# Schematic_R1.net
KiCad netlist of a schematic drawn in Altium Designer
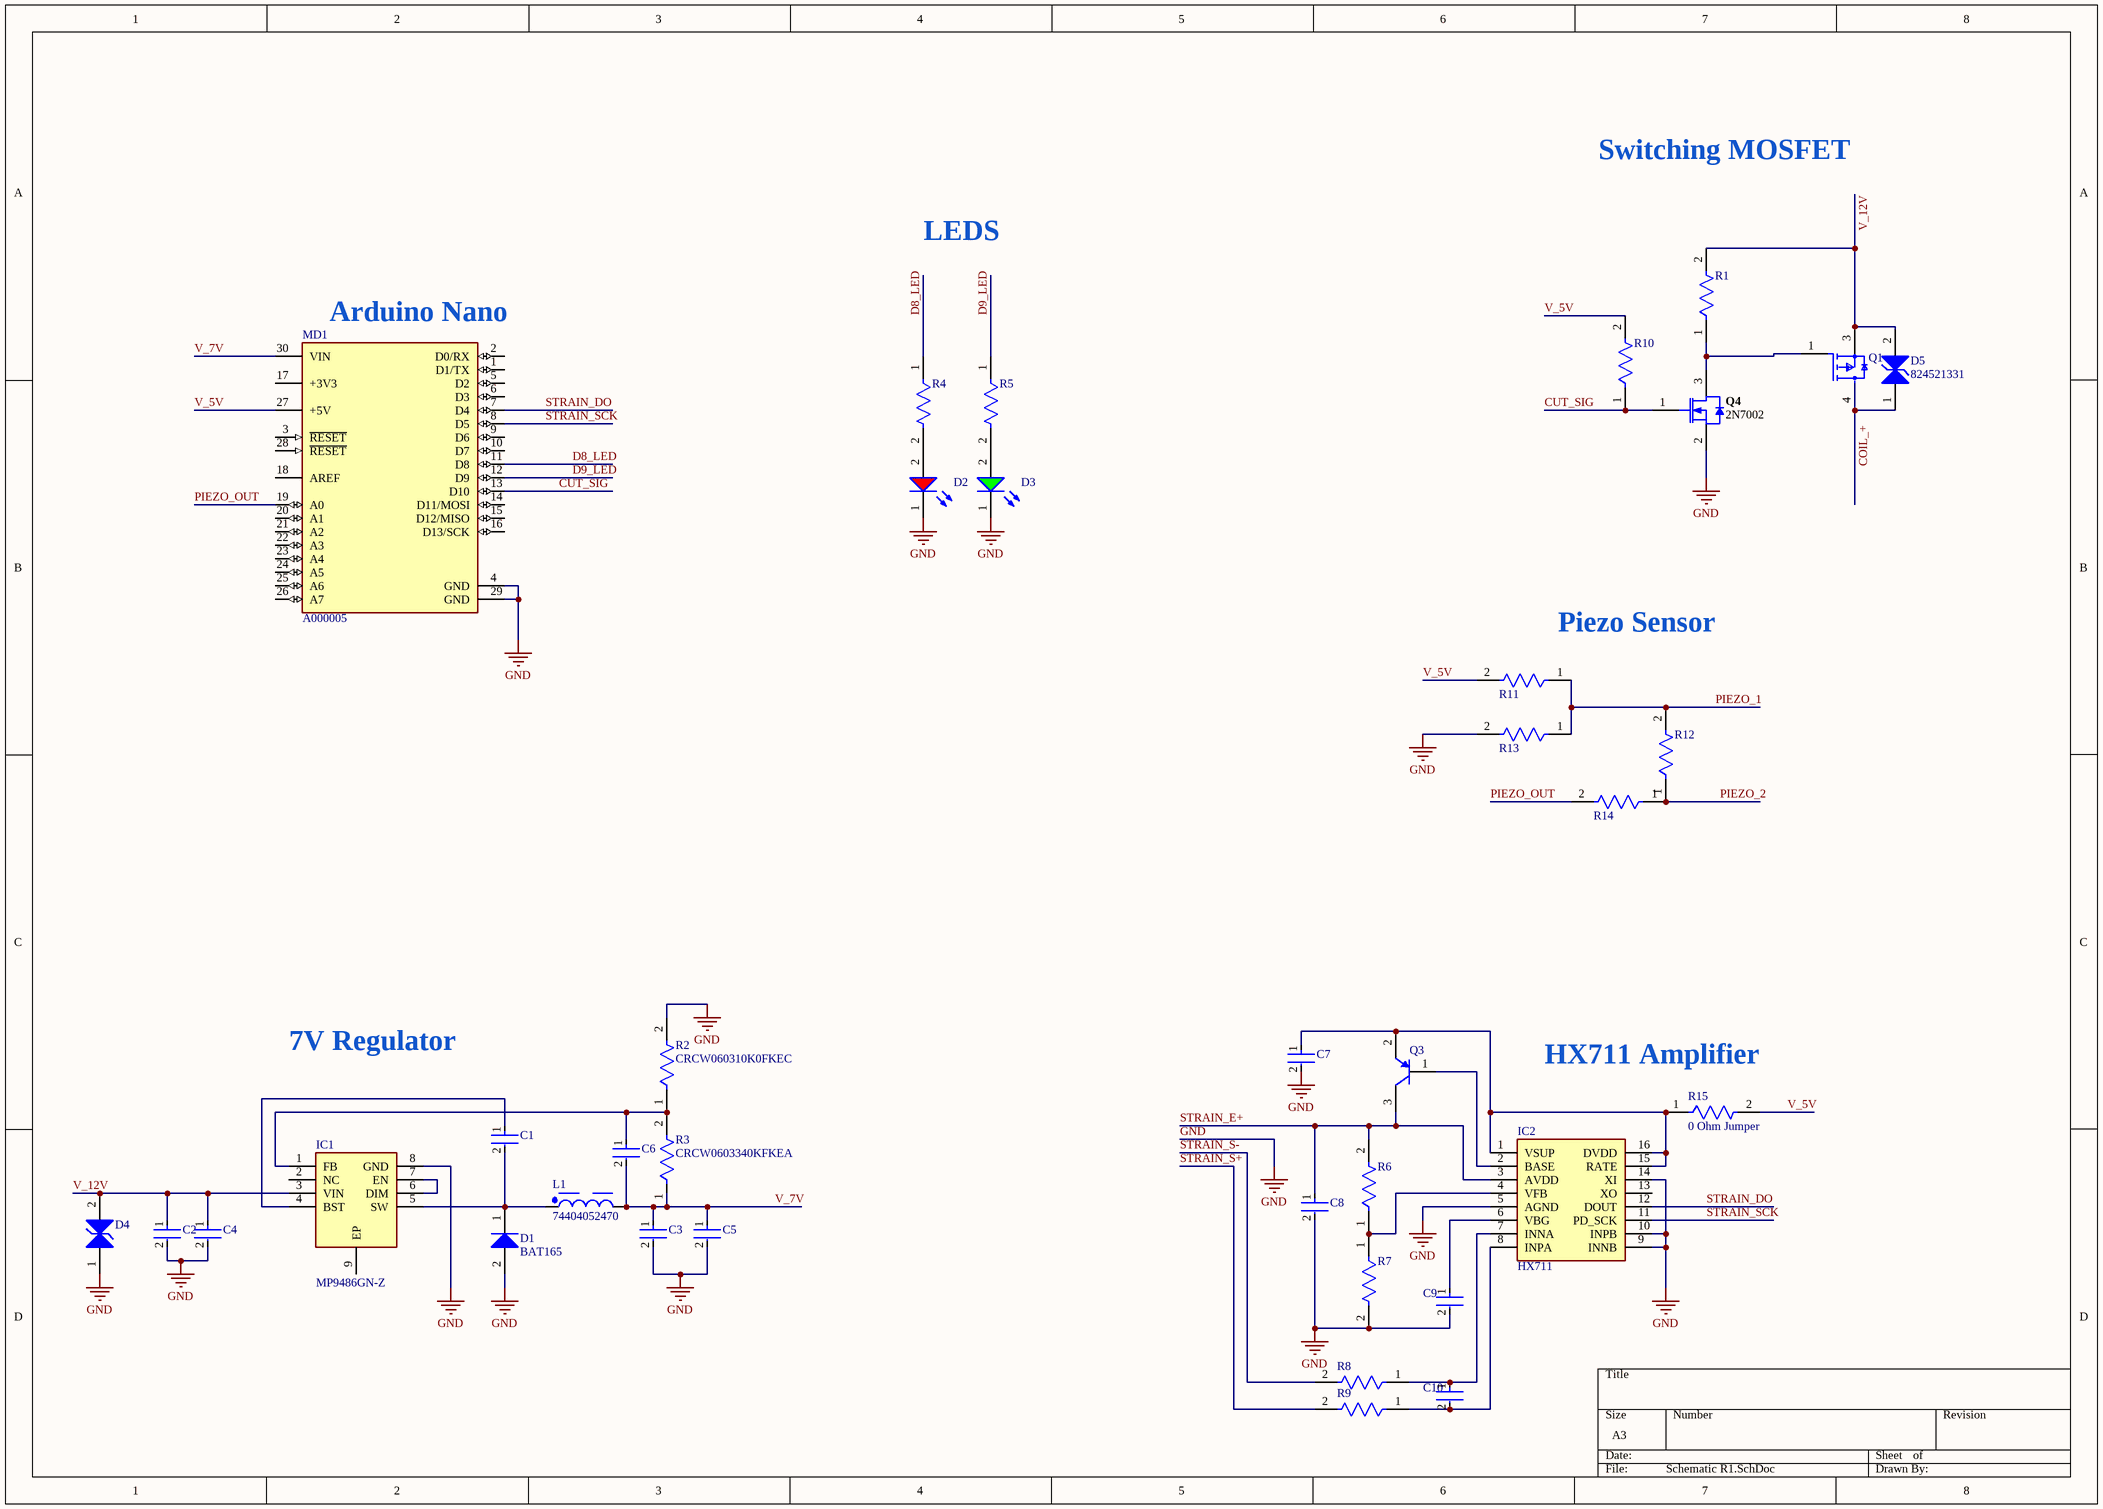
[diagram p0: Schematic R1.SchDoc]

(export (version "E")
  (design (tool "Eeschema 10.0.6"))
  (components
    (comp (ref "C1")
      (value "C0603C104K3PACTU")
      (footprint "FP-C0603C-CF-MFG")
      (description "C0603 0.10 μF X5R 30ppm/°C 10.00% 25 V")
      (fields
        (field (name "TOLERANCE") "0.1")
        (field (name "OCTOPART") "https://octopart.com/c0603c104k3pactu-kemet-19022554")
      )
      (libsource (lib "Altium Content Vault") (part "b4654b650e69147ec39a6b967a45e02"))
    )
    (comp (ref "C2")
      (value "C3216X5R1E476M160AC")
      (footprint "FP-C3216-160-0_2-MFG")
      (description "Multilayer Ceramic Capacitors 47uF ±20% 25V X5R SMD 1206")
      (fields (field (name "VOLTAGE") "25V") (field (name "TOLERANCE") "20%"))
      (libsource (lib "Altium Content Vault") (part "11868f565c42a9108669ba33697ecf6"))
    )
    (comp (ref "C3")
      (value "C3216X5R1E476M160AC")
      (footprint "FP-C3216-160-0_2-MFG")
      (description "Multilayer Ceramic Capacitors 47uF ±20% 25V X5R SMD 1206")
      (fields (field (name "VOLTAGE") "25V") (field (name "TOLERANCE") "20%"))
      (libsource (lib "Altium Content Vault") (part "11868f565c42a9108669ba33697ecf6"))
    )
    (comp (ref "C4")
      (value "C0603C104K3PACTU")
      (footprint "FP-C0603C-CF-MFG")
      (description "C0603 0.10 μF X5R 30ppm/°C 10.00% 25 V")
      (fields
        (field (name "TOLERANCE") "0.1")
        (field (name "OCTOPART") "https://octopart.com/c0603c104k3pactu-kemet-19022554")
      )
      (libsource (lib "Altium Content Vault") (part "b4654b650e69147ec39a6b967a45e02"))
    )
    (comp (ref "C5")
      (value "C0603C225K4PACTU")
      (footprint "FP-C0603C225K4PACTU-MFG")
      (description "CAP CER 2.2UF 16V X5R 0603")
      (fields (field (name "TOLERANCE") "10%") (field (name "VOLTAGE") "16V"))
      (libsource (lib "Altium Content Vault") (part "b4654b650e69147ec39a6b967a45e02"))
    )
    (comp (ref "C6")
      (value "C0603C104K3PACTU")
      (footprint "FP-C0603C-CF-MFG")
      (description "C0603 0.10 μF X5R 30ppm/°C 10.00% 25 V")
      (fields
        (field (name "TOLERANCE") "0.1")
        (field (name "OCTOPART") "https://octopart.com/c0603c104k3pactu-kemet-19022554")
      )
      (libsource (lib "Altium Content Vault") (part "b4654b650e69147ec39a6b967a45e02"))
    )
    (comp (ref "C7")
      (value "C0603C106M8PACTU")
      (footprint "FP-C0603C106M8PACTU-MFG")
      (description "CAP CER 10UF 10V X5R 0603")
      (libsource (lib "Altium Content Vault") (part "02cd4be3c70576c341d710602a673aa"))
    )
    (comp (ref "C8")
      (value "C0603C106M8PACTU")
      (footprint "FP-C0603C106M8PACTU-MFG")
      (description "CAP CER 10UF 10V X5R 0603")
      (libsource (lib "Altium Content Vault") (part "02cd4be3c70576c341d710602a673aa"))
    )
    (comp (ref "C9")
      (value "C0603C104K3PACTU")
      (footprint "FP-C0603C-CF-MFG")
      (description "C0603 0.10 μF X5R 30ppm/°C 10.00% 25 V")
      (fields
        (field (name "TOLERANCE") "0.1")
        (field (name "OCTOPART") "https://octopart.com/c0603c104k3pactu-kemet-19022554")
      )
      (libsource (lib "Altium Content Vault") (part "b4654b650e69147ec39a6b967a45e02"))
    )
    (comp (ref "C10")
      (value "C0603C104K3PACTU")
      (footprint "FP-C0603C-CF-MFG")
      (description "C0603 0.10 μF X5R 30ppm/°C 10.00% 25 V")
      (fields
        (field (name "TOLERANCE") "0.1")
        (field (name "OCTOPART") "https://octopart.com/c0603c104k3pactu-kemet-19022554")
      )
      (libsource (lib "Altium Content Vault") (part "b4654b650e69147ec39a6b967a45e02"))
    )
    (comp (ref "D1")
      (value "BAT165")
      (footprint "INF-SOD323_V")
      (description "Medium Power AF Schottky Diode, SOD323, Reel, Green")
      (fields (field (name "MANUFACTURER") "Infineon"))
      (libsource (lib "Altium Content Vault") (part "INF-D_K1A2-2"))
    )
    (comp (ref "D2")
      (value "150080RS75000")
      (footprint "WL-SMCW_0805_150080xx75000")
      (libsource (lib "Altium Content Vault") (part "LED_Red_2A-1K"))
    )
    (comp (ref "D3")
      (value "150080GS75000")
      (footprint "WL-SMCW_0805_150080xx75000")
      (libsource (lib "Altium Content Vault") (part "LED_Green_2A-1K"))
    )
    (comp (ref "D4")
      (value "824521331")
      (footprint "WE-TVSP_DO-214AA_Bidirectional")
      (description "824521331 TVS diode [Würth Elektronik] 824521331 TVS diode")
      (libsource (lib "Altium Content Vault") (part "WE-TVSP_Bidirectional"))
    )
    (comp (ref "D5")
      (value "824521331")
      (footprint "WE-TVSP_DO-214AA_Bidirectional")
      (description "824521331 TVS diode [Würth Elektronik] 824521331 TVS diode")
      (libsource (lib "Altium Content Vault") (part "WE-TVSP_Bidirectional"))
    )
    (comp (ref "IC1")
      (value "MP9486GN-Z")
      (footprint "SamacSys:SOIC127P600X170-9N")
      (description "Integrated Circuit")
      (fields (field (name "MOUSER PART NUMBER") "946-MP9486GN-Z"))
      (libsource (lib "*") (part "MP9486GN-Z"))
    )
    (comp (ref "IC2")
      (value "HX711")
      (footprint "SamacSys:SOIC127P600X160-16N")
      (description "Integrated Circuit")
      (libsource (lib "*") (part "HX711"))
    )
    (comp (ref "L1")
      (value "74404052470")
      (footprint "WE-LQS_5020")
      (description "74404052470 Inductors, Fixed, WE-LQS SMD 5020 47uH 0.8A 521mOhms")
      (fields (field (name "TOLERANCE") "20%"))
      (libsource (lib "Altium Content Vault") (part "Inductor - 2"))
    )
    (comp (ref "MD1")
      (value "A000005")
      (footprint "FP-A000005-MFG")
      (description "ARDUINO NANO ATMEGA328 EVAL BRD")
      (libsource (lib "Altium Content Vault") (part "d190c066e99afd1c6882cf92e11b2cc"))
    )
    (comp (ref "Q1")
      (value "SQM120P06-07L_GE3")
      (footprint "FP-T13-0707-MFG")
      (description "MOSFET P-CH 60V 120A TO263")
      (fields
        (field (name "MANUFACTURER") "Vishay")
        (field (name "OCTOPART") "https://octopart.com/sqm120p06-07l_ge3-vishay-61925110")
      )
      (libsource (lib "Altium Content Vault") (part "b4396205e6ce7dccbaef9df51870b92"))
    )
    (comp (ref "Q3")
      (value "MMBT4403LT1G")
      (footprint "ONSC-SOT-23-3-318-08_V")
      (description "Switching Transistor, PNP Silicon, 3-Pin SOT-23, Pb-Free, Tape and Reel")
      (fields (field (name "MANUFACTURER") "On Semiconductor"))
      (libsource (lib "Altium Content Vault") (part "ONSC-PNP-B1E2C3-3"))
    )
    (comp (ref "Q4")
      (value "2N7002")
      (footprint "INF-PG-SOT23_M")
      (fields (field (name "MANUFACTURER") "Infineon"))
      (libsource (lib "Altium Content Vault") (part "INF-NDMOS-GSD-3"))
    )
    (comp (ref "R1")
      (value "CRCW060310K0FKEC")
      (footprint "FP-CRCW0603-e3-IPC_A")
      (description "RES Thick Film, 10kΩ, 1%, 0.1W, 100ppm/°C, 0603")
      (fields (field (name "TOLERANCE") "1%"))
      (libsource (lib "Altium Content Vault") (part "1029c3af85768c4190bb7ad29bc67b5"))
    )
    (comp (ref "R2")
      (value "CRCW060310K0FKEC")
      (footprint "FP-CRCW0603-e3-IPC_A")
      (description "RES Thick Film, 10kΩ, 1%, 0.1W, 100ppm/°C, 0603")
      (fields (field (name "TOLERANCE") "1%"))
      (libsource (lib "Altium Content Vault") (part "1029c3af85768c4190bb7ad29bc67b5"))
    )
    (comp (ref "R3")
      (value "CRCW0603340KFKEA")
      (footprint "FP-CRCW0603-e3-IPC_C")
      (description "RES Thick Film, 340kΩ, 1%, 0.1W, 100ppm/°C, 0603")
      (fields (field (name "TOLERANCE") "1%"))
      (libsource (lib "Altium Content Vault") (part "1029c3af85768c4190bb7ad29bc67b5"))
    )
    (comp (ref "R4")
      (value "CRCW0603470RFKEA")
      (footprint "FP-CRCW0603-e3-MFG")
      (description "RES Thick Film, 470Ω, 1%, 0.1W, 100ppm/°C, 0603")
      (fields (field (name "TOLERANCE") "1%"))
      (libsource (lib "Altium Content Vault") (part "1029c3af85768c4190bb7ad29bc67b5"))
    )
    (comp (ref "R5")
      (value "CRCW0603470RFKEA")
      (footprint "FP-CRCW0603-e3-MFG")
      (description "RES Thick Film, 470Ω, 1%, 0.1W, 100ppm/°C, 0603")
      (fields (field (name "TOLERANCE") "1%"))
      (libsource (lib "Altium Content Vault") (part "1029c3af85768c4190bb7ad29bc67b5"))
    )
    (comp (ref "R6")
      (value "CRCW060310K0FKEC")
      (footprint "FP-CRCW0603-e3-IPC_A")
      (description "RES Thick Film, 10kΩ, 1%, 0.1W, 100ppm/°C, 0603")
      (fields (field (name "TOLERANCE") "1%"))
      (libsource (lib "Altium Content Vault") (part "1029c3af85768c4190bb7ad29bc67b5"))
    )
    (comp (ref "R7")
      (value "CRCW06038K20FKEC")
      (footprint "FP-CRCW0603-e3-IPC_B")
      (description "RES Thick Film, 8.2kΩ, 1%, 0.1W, 100ppm/°C, 0603")
      (fields (field (name "TOLERANCE") "1%"))
      (libsource (lib "Altium Content Vault") (part "1029c3af85768c4190bb7ad29bc67b5"))
    )
    (comp (ref "R8")
      (value "CRCW0603100RFKEB")
      (footprint "FP-CRCW0603-e3-IPC_A")
      (description "RES Thick Film, 100Ω, 1%, 0.1W, 100ppm/°C, 0603")
      (fields (field (name "TOLERANCE") "1%"))
      (libsource (lib "Altium Content Vault") (part "1029c3af85768c4190bb7ad29bc67b5"))
    )
    (comp (ref "R9")
      (value "CRCW0603100RFKEB")
      (footprint "FP-CRCW0603-e3-IPC_A")
      (description "RES Thick Film, 100Ω, 1%, 0.1W, 100ppm/°C, 0603")
      (fields (field (name "TOLERANCE") "1%"))
      (libsource (lib "Altium Content Vault") (part "1029c3af85768c4190bb7ad29bc67b5"))
    )
    (comp (ref "R10")
      (value "CRCW060310K0FKEC")
      (footprint "FP-CRCW0603-e3-IPC_A")
      (description "RES Thick Film, 10kΩ, 1%, 0.1W, 100ppm/°C, 0603")
      (fields (field (name "TOLERANCE") "1%"))
      (libsource (lib "Altium Content Vault") (part "1029c3af85768c4190bb7ad29bc67b5"))
    )
    (comp (ref "R11")
      (value "CRCW060310K0FKEC")
      (footprint "FP-CRCW0603-e3-IPC_A")
      (description "RES Thick Film, 10kΩ, 1%, 0.1W, 100ppm/°C, 0603")
      (fields (field (name "TOLERANCE") "1%"))
      (libsource (lib "Altium Content Vault") (part "1029c3af85768c4190bb7ad29bc67b5"))
    )
    (comp (ref "R12")
      (value "CRCW060310M0JNEA")
      (footprint "FP-CRCW0603-e3-IPC_A")
      (description "RES Thick Film, 10MΩ, 5%, 0.1W, 200ppm/°C, 0603")
      (fields (field (name "TOLERANCE") "5%"))
      (libsource (lib "Altium Content Vault") (part "1029c3af85768c4190bb7ad29bc67b5"))
    )
    (comp (ref "R13")
      (value "CRCW060310K0FKEC")
      (footprint "FP-CRCW0603-e3-IPC_A")
      (description "RES Thick Film, 10kΩ, 1%, 0.1W, 100ppm/°C, 0603")
      (fields (field (name "TOLERANCE") "1%"))
      (libsource (lib "Altium Content Vault") (part "1029c3af85768c4190bb7ad29bc67b5"))
    )
    (comp (ref "R14")
      (value "CRCW060310K0FKEC")
      (footprint "FP-CRCW0603-e3-IPC_A")
      (description "RES Thick Film, 10kΩ, 1%, 0.1W, 100ppm/°C, 0603")
      (fields (field (name "TOLERANCE") "1%"))
      (libsource (lib "Altium Content Vault") (part "1029c3af85768c4190bb7ad29bc67b5"))
    )
    (comp (ref "R15")
      (value "0 Ohm Jumper")
      (footprint "FP-CRCW0603-HPe3-IPC_B")
      (description "RES Thick Film, 0Ω, 5%, 0.33W, 200ppm/°C, 0603")
      (libsource (lib "Altium Content Vault") (part "1029c3af85768c4190bb7ad29bc67b5"))
    )
  )
  (nets
    (net (code "1") (name "/COIL_+") (class "Default")
      (node (ref "D5") (pin "1") (pinfunction "1_1") (pintype "passive"))
      (node (ref "Q1") (pin "4") (pinfunction "D_4") (pintype "passive"))
    )
    (net (code "2") (name "/CUT_SIG") (class "Default")
      (node (ref "MD1") (pin "13") (pinfunction "D10_13") (pintype "bidirectional"))
      (node (ref "Q4") (pin "1") (pinfunction "GATE_1") (pintype "passive"))
      (node (ref "R10") (pin "1") (pinfunction "1_1") (pintype "passive"))
    )
    (net (code "3") (name "/D8_LED") (class "Default")
      (node (ref "MD1") (pin "11") (pinfunction "D8_11") (pintype "bidirectional"))
      (node (ref "R4") (pin "1") (pinfunction "1_1") (pintype "passive"))
    )
    (net (code "4") (name "/D9_LED") (class "Default")
      (node (ref "MD1") (pin "12") (pinfunction "D9_12") (pintype "bidirectional"))
      (node (ref "R5") (pin "1") (pinfunction "1_1") (pintype "passive"))
    )
    (net (code "5") (name "/PIEZO_1") (class "Default")
      (node (ref "R11") (pin "1") (pinfunction "1_1") (pintype "passive"))
      (node (ref "R12") (pin "2") (pinfunction "2_2") (pintype "passive"))
      (node (ref "R13") (pin "1") (pinfunction "1_1") (pintype "passive"))
    )
    (net (code "6") (name "/PIEZO_2") (class "Default")
      (node (ref "R12") (pin "1") (pinfunction "1_1") (pintype "passive"))
      (node (ref "R14") (pin "1") (pinfunction "1_1") (pintype "passive"))
    )
    (net (code "7") (name "/PIEZO_OUT") (class "Default")
      (node (ref "MD1") (pin "19") (pinfunction "A0_19") (pintype "bidirectional"))
      (node (ref "R14") (pin "2") (pinfunction "2_2") (pintype "passive"))
    )
    (net (code "8") (name "/STRAIN_DO") (class "Default")
      (node (ref "IC2") (pin "12") (pinfunction "DOUT_12") (pintype "passive"))
      (node (ref "MD1") (pin "7") (pinfunction "D4_7") (pintype "bidirectional"))
    )
    (net (code "9") (name "/STRAIN_E+") (class "Default")
      (node (ref "C8") (pin "1") (pinfunction "1_1") (pintype "passive"))
      (node (ref "IC2") (pin "3") (pinfunction "AVDD_3") (pintype "passive"))
      (node (ref "Q3") (pin "3") (pinfunction "C_3") (pintype "passive"))
      (node (ref "R6") (pin "2") (pinfunction "2_2") (pintype "passive"))
    )
    (net (code "10") (name "/STRAIN_S+") (class "Default")
      (node (ref "R9") (pin "2") (pinfunction "2_2") (pintype "passive"))
    )
    (net (code "11") (name "/STRAIN_S-") (class "Default")
      (node (ref "R8") (pin "2") (pinfunction "2_2") (pintype "passive"))
    )
    (net (code "12") (name "/STRAIN_SCK") (class "Default")
      (node (ref "IC2") (pin "11") (pinfunction "PD_SCK_11") (pintype "passive"))
      (node (ref "MD1") (pin "8") (pinfunction "D5_8") (pintype "bidirectional"))
    )
    (net (code "13") (name "/V_5V") (class "Default")
      (node (ref "MD1") (pin "27") (pinfunction "+5V_27") (pintype "power_in"))
      (node (ref "R10") (pin "2") (pinfunction "2_2") (pintype "passive"))
      (node (ref "R11") (pin "2") (pinfunction "2_2") (pintype "passive"))
      (node (ref "R15") (pin "2") (pinfunction "2_2") (pintype "passive"))
    )
    (net (code "14") (name "/V_7V") (class "Default")
      (node (ref "C3") (pin "1") (pinfunction "1_1") (pintype "passive"))
      (node (ref "C5") (pin "1") (pinfunction "1_1") (pintype "passive"))
      (node (ref "C6") (pin "2") (pinfunction "2_2") (pintype "passive"))
      (node (ref "L1") (pin "2") (pinfunction "2_2") (pintype "passive"))
      (node (ref "MD1") (pin "30") (pinfunction "VIN_30") (pintype "power_in"))
      (node (ref "R3") (pin "1") (pinfunction "1_1") (pintype "passive"))
    )
    (net (code "15") (name "/V_12V") (class "Default")
      (node (ref "C2") (pin "1") (pinfunction "1_1") (pintype "passive"))
      (node (ref "C4") (pin "1") (pinfunction "1_1") (pintype "passive"))
      (node (ref "D4") (pin "2") (pinfunction "2_2") (pintype "passive"))
      (node (ref "D5") (pin "2") (pinfunction "2_2") (pintype "passive"))
      (node (ref "IC1") (pin "3") (pinfunction "VIN_3") (pintype "passive"))
      (node (ref "Q1") (pin "3") (pinfunction "S_3") (pintype "passive"))
      (node (ref "R1") (pin "2") (pinfunction "2_2") (pintype "passive"))
    )
    (net (code "16") (name "GND") (class "Default")
      (node (ref "C2") (pin "2") (pinfunction "2_2") (pintype "passive"))
      (node (ref "C3") (pin "2") (pinfunction "2_2") (pintype "passive"))
      (node (ref "C4") (pin "2") (pinfunction "2_2") (pintype "passive"))
      (node (ref "C5") (pin "2") (pinfunction "2_2") (pintype "passive"))
      (node (ref "C7") (pin "2") (pinfunction "2_2") (pintype "passive"))
      (node (ref "C8") (pin "2") (pinfunction "2_2") (pintype "passive"))
      (node (ref "C9") (pin "2") (pinfunction "2_2") (pintype "passive"))
      (node (ref "D1") (pin "2") (pinfunction "A_2") (pintype "passive"))
      (node (ref "D2") (pin "1") (pinfunction "K_1") (pintype "passive"))
      (node (ref "D3") (pin "1") (pinfunction "K_1") (pintype "passive"))
      (node (ref "D4") (pin "1") (pinfunction "1_1") (pintype "passive"))
      (node (ref "IC1") (pin "8") (pinfunction "GND_8") (pintype "passive"))
      (node (ref "IC2") (pin "10") (pinfunction "INPB_10") (pintype "passive"))
      (node (ref "IC2") (pin "14") (pinfunction "XI_14") (pintype "passive"))
      (node (ref "IC2") (pin "5") (pinfunction "AGND_5") (pintype "passive"))
      (node (ref "IC2") (pin "9") (pinfunction "INNB_9") (pintype "passive"))
      (node (ref "MD1") (pin "29") (pinfunction "GND_29") (pintype "power_in"))
      (node (ref "MD1") (pin "4") (pinfunction "GND_4") (pintype "power_in"))
      (node (ref "Q4") (pin "2") (pinfunction "SOURCE_2") (pintype "passive"))
      (node (ref "R13") (pin "2") (pinfunction "2_2") (pintype "passive"))
      (node (ref "R2") (pin "2") (pinfunction "2_2") (pintype "passive"))
      (node (ref "R7") (pin "2") (pinfunction "2_2") (pintype "passive"))
    )
    (net (code "17") (name "Net-(D1-K)") (class "Default")
      (node (ref "C1") (pin "2") (pinfunction "2_2") (pintype "passive"))
      (node (ref "D1") (pin "1") (pinfunction "K_1") (pintype "passive"))
      (node (ref "IC1") (pin "5") (pinfunction "SW_5") (pintype "passive"))
      (node (ref "L1") (pin "1") (pinfunction "1_1") (pintype "passive"))
    )
    (net (code "18") (name "Net-(D2-A)") (class "Default")
      (node (ref "D2") (pin "2") (pinfunction "A_2") (pintype "passive"))
      (node (ref "R4") (pin "2") (pinfunction "2_2") (pintype "passive"))
    )
    (net (code "19") (name "Net-(D3-A)") (class "Default")
      (node (ref "D3") (pin "2") (pinfunction "A_2") (pintype "passive"))
      (node (ref "R5") (pin "2") (pinfunction "2_2") (pintype "passive"))
    )
    (net (code "20") (name "Net-(IC1-BST)") (class "Default")
      (node (ref "C1") (pin "1") (pinfunction "1_1") (pintype "passive"))
      (node (ref "IC1") (pin "4") (pinfunction "BST_4") (pintype "passive"))
    )
    (net (code "21") (name "Net-(IC1-DIM)") (class "Default")
      (node (ref "IC1") (pin "6") (pinfunction "DIM_6") (pintype "passive"))
      (node (ref "IC1") (pin "7") (pinfunction "EN_7") (pintype "passive"))
    )
    (net (code "22") (name "Net-(IC1-FB)") (class "Default")
      (node (ref "C6") (pin "1") (pinfunction "1_1") (pintype "passive"))
      (node (ref "IC1") (pin "1") (pinfunction "FB_1") (pintype "passive"))
      (node (ref "R2") (pin "1") (pinfunction "1_1") (pintype "passive"))
      (node (ref "R3") (pin "2") (pinfunction "2_2") (pintype "passive"))
    )
    (net (code "23") (name "Net-(IC2-BASE)") (class "Default")
      (node (ref "IC2") (pin "2") (pinfunction "BASE_2") (pintype "passive"))
      (node (ref "Q3") (pin "1") (pinfunction "B_1") (pintype "passive"))
    )
    (net (code "24") (name "Net-(IC2-DVDD)") (class "Default")
      (node (ref "C7") (pin "1") (pinfunction "1_1") (pintype "passive"))
      (node (ref "IC2") (pin "1") (pinfunction "VSUP_1") (pintype "passive"))
      (node (ref "IC2") (pin "15") (pinfunction "RATE_15") (pintype "passive"))
      (node (ref "IC2") (pin "16") (pinfunction "DVDD_16") (pintype "passive"))
      (node (ref "Q3") (pin "2") (pinfunction "E_2") (pintype "passive"))
      (node (ref "R15") (pin "1") (pinfunction "1_1") (pintype "passive"))
    )
    (net (code "25") (name "Net-(IC2-INNA)") (class "Default")
      (node (ref "C10") (pin "1") (pinfunction "1_1") (pintype "passive"))
      (node (ref "IC2") (pin "7") (pinfunction "INNA_7") (pintype "passive"))
      (node (ref "R8") (pin "1") (pinfunction "1_1") (pintype "passive"))
    )
    (net (code "26") (name "Net-(IC2-INPA)") (class "Default")
      (node (ref "C10") (pin "2") (pinfunction "2_2") (pintype "passive"))
      (node (ref "IC2") (pin "8") (pinfunction "INPA_8") (pintype "passive"))
      (node (ref "R9") (pin "1") (pinfunction "1_1") (pintype "passive"))
    )
    (net (code "27") (name "Net-(IC2-VBG)") (class "Default")
      (node (ref "C9") (pin "1") (pinfunction "1_1") (pintype "passive"))
      (node (ref "IC2") (pin "6") (pinfunction "VBG_6") (pintype "passive"))
    )
    (net (code "28") (name "Net-(IC2-VFB)") (class "Default")
      (node (ref "IC2") (pin "4") (pinfunction "VFB_4") (pintype "passive"))
      (node (ref "R6") (pin "1") (pinfunction "1_1") (pintype "passive"))
      (node (ref "R7") (pin "1") (pinfunction "1_1") (pintype "passive"))
    )
    (net (code "29") (name "Net-(Q1-G)") (class "Default")
      (node (ref "Q1") (pin "1") (pinfunction "G_1") (pintype "passive"))
      (node (ref "Q4") (pin "3") (pinfunction "DRAIN_3") (pintype "passive"))
      (node (ref "R1") (pin "1") (pinfunction "1_1") (pintype "passive"))
    )
    (net (code "30") (name "unconnected-(IC1-EP-Pad9)") (class "Default")
      (node (ref "IC1") (pin "9") (pinfunction "EP_9") (pintype "passive"))
    )
    (net (code "31") (name "unconnected-(IC1-NC-Pad2)") (class "Default")
      (node (ref "IC1") (pin "2") (pinfunction "NC_2") (pintype "passive"))
    )
    (net (code "32") (name "unconnected-(IC2-XO-Pad13)") (class "Default")
      (node (ref "IC2") (pin "13") (pinfunction "XO_13") (pintype "passive"))
    )
    (net (code "33") (name "unconnected-(MD1-+3V3-Pad17)") (class "Default")
      (node (ref "MD1") (pin "17") (pinfunction "+3V3_17") (pintype "power_in"))
    )
    (net (code "34") (name "unconnected-(MD1-A1-Pad20)") (class "Default")
      (node (ref "MD1") (pin "20") (pinfunction "A1_20") (pintype "bidirectional"))
    )
    (net (code "35") (name "unconnected-(MD1-A2-Pad21)") (class "Default")
      (node (ref "MD1") (pin "21") (pinfunction "A2_21") (pintype "bidirectional"))
    )
    (net (code "36") (name "unconnected-(MD1-A3-Pad22)") (class "Default")
      (node (ref "MD1") (pin "22") (pinfunction "A3_22") (pintype "bidirectional"))
    )
    (net (code "37") (name "unconnected-(MD1-A4-Pad23)") (class "Default")
      (node (ref "MD1") (pin "23") (pinfunction "A4_23") (pintype "bidirectional"))
    )
    (net (code "38") (name "unconnected-(MD1-A5-Pad24)") (class "Default")
      (node (ref "MD1") (pin "24") (pinfunction "A5_24") (pintype "bidirectional"))
    )
    (net (code "39") (name "unconnected-(MD1-A6-Pad25)") (class "Default")
      (node (ref "MD1") (pin "25") (pinfunction "A6_25") (pintype "bidirectional"))
    )
    (net (code "40") (name "unconnected-(MD1-A7-Pad26)") (class "Default")
      (node (ref "MD1") (pin "26") (pinfunction "A7_26") (pintype "bidirectional"))
    )
    (net (code "41") (name "unconnected-(MD1-AREF-Pad18)") (class "Default")
      (node (ref "MD1") (pin "18") (pinfunction "AREF_18") (pintype "passive"))
    )
    (net (code "42") (name "unconnected-(MD1-D0{slash}RX-Pad2)") (class "Default")
      (node (ref "MD1") (pin "2") (pinfunction "D0/RX_2") (pintype "bidirectional"))
    )
    (net (code "43") (name "unconnected-(MD1-D1{slash}TX-Pad1)") (class "Default")
      (node (ref "MD1") (pin "1") (pinfunction "D1/TX_1") (pintype "bidirectional"))
    )
    (net (code "44") (name "unconnected-(MD1-D2-Pad5)") (class "Default")
      (node (ref "MD1") (pin "5") (pinfunction "D2_5") (pintype "bidirectional"))
    )
    (net (code "45") (name "unconnected-(MD1-D3-Pad6)") (class "Default")
      (node (ref "MD1") (pin "6") (pinfunction "D3_6") (pintype "bidirectional"))
    )
    (net (code "46") (name "unconnected-(MD1-D6-Pad9)") (class "Default")
      (node (ref "MD1") (pin "9") (pinfunction "D6_9") (pintype "bidirectional"))
    )
    (net (code "47") (name "unconnected-(MD1-D7-Pad10)") (class "Default")
      (node (ref "MD1") (pin "10") (pinfunction "D7_10") (pintype "bidirectional"))
    )
    (net (code "48") (name "unconnected-(MD1-D11{slash}MOSI-Pad14)") (class "Default")
      (node (ref "MD1") (pin "14") (pinfunction "D11/MOSI_14") (pintype "bidirectional"))
    )
    (net (code "49") (name "unconnected-(MD1-D12{slash}MISO-Pad15)") (class "Default")
      (node (ref "MD1") (pin "15") (pinfunction "D12/MISO_15") (pintype "bidirectional"))
    )
    (net (code "50") (name "unconnected-(MD1-D13{slash}SCK-Pad16)") (class "Default")
      (node (ref "MD1") (pin "16") (pinfunction "D13/SCK_16") (pintype "bidirectional"))
    )
    (net (code "51") (name "unconnected-(MD1-~{RESET}-Pad3)") (class "Default")
      (node (ref "MD1") (pin "3") (pinfunction "~{RESET}_3") (pintype "input"))
    )
    (net (code "52") (name "unconnected-(MD1-~{RESET}-Pad28)") (class "Default")
      (node (ref "MD1") (pin "28") (pinfunction "~{RESET}_28") (pintype "input"))
    )
  )
)
